# ProPrj_rp-nano-4_2025-11-21.net
KiCad netlist of a schematic drawn in EasyEDA Pro
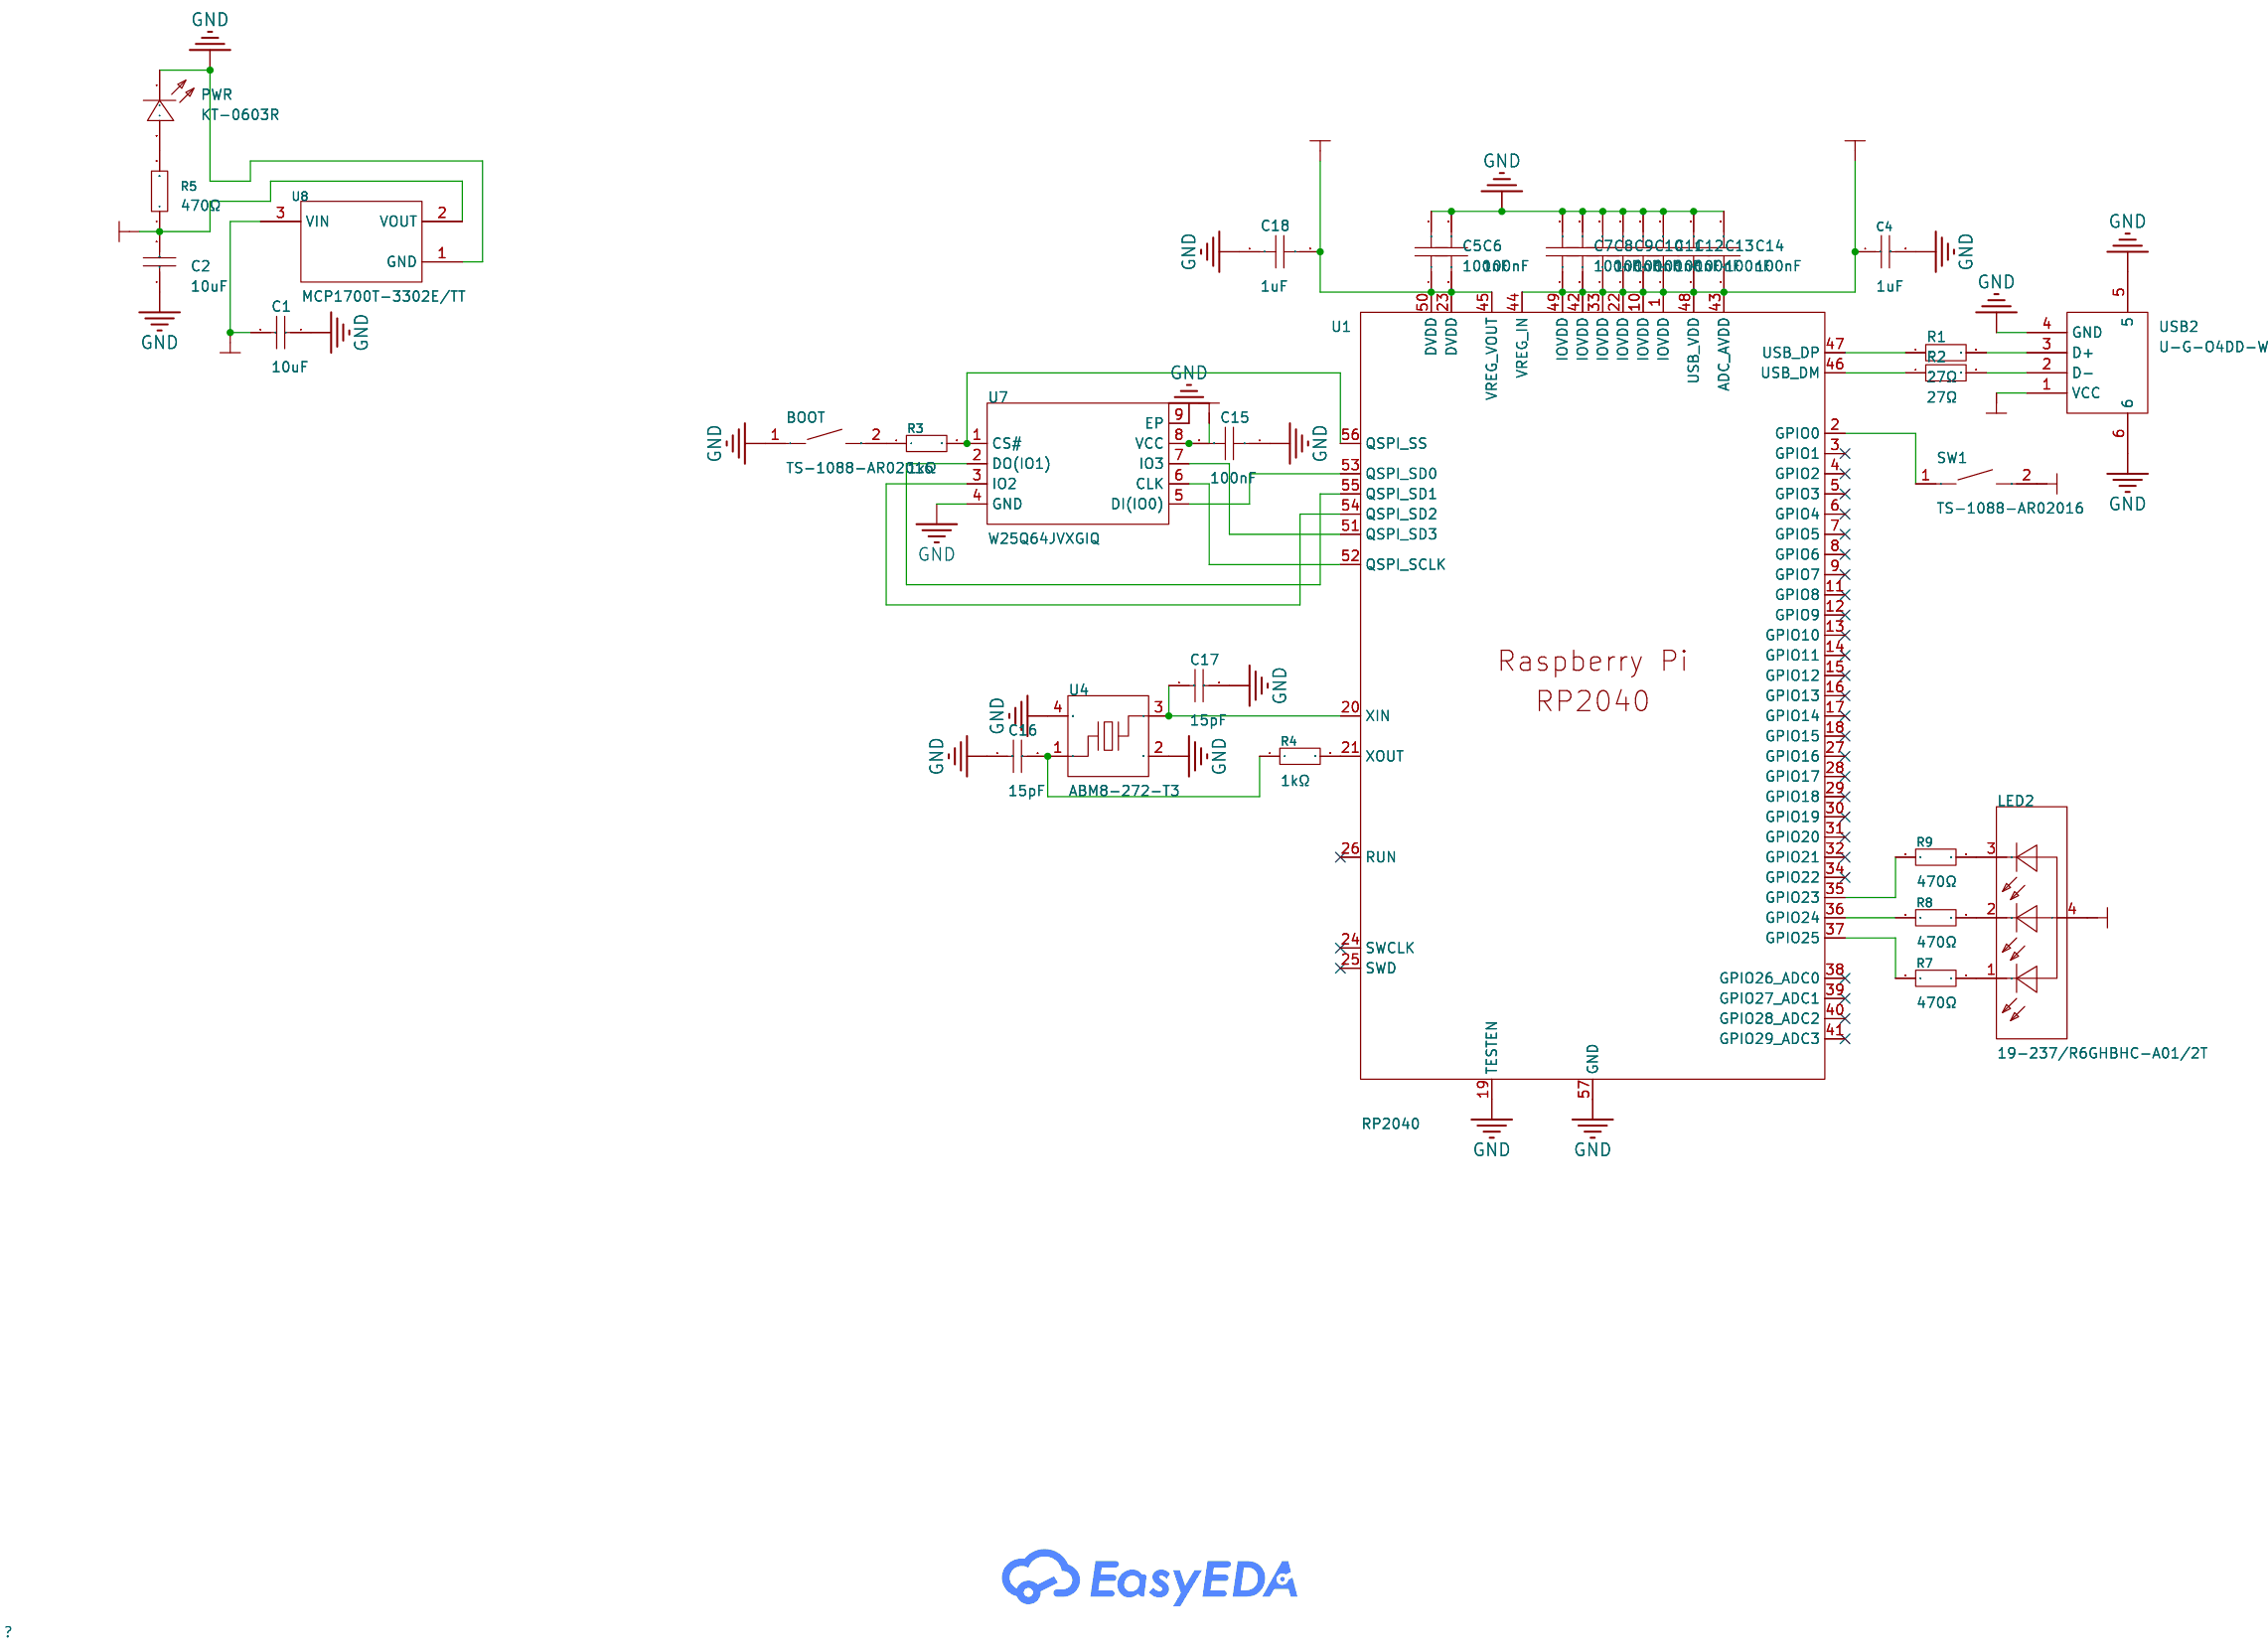
[diagram p0: schematic sheet]

(export (version "E")
  (design (tool "Eeschema 10.0.6"))
  (components
    (comp (ref "BOOT")
      (value "TS-1088-AR02016")
      (footprint "easyedapro:SW-SMD_L3.9-W3.0-P4.45")
      (fields (field (name "Manufacturer") "XUNPU(讯普)"))
      (libsource (lib "easyedapro") (part "TS-1088-AR02016"))
    )
    (comp (ref "C1")
      (value "10uF")
      (footprint "easyedapro:C0402")
      (fields
        (field (name "Manufacturer Part") "CL05A106MQ5NUNC")
        (field (name "Manufacturer") "SAMSUNG(三星)")
      )
      (libsource (lib "easyedapro") (part "CL05A106MQ5NUNC"))
    )
    (comp (ref "C2")
      (value "10uF")
      (footprint "easyedapro:C0402")
      (fields
        (field (name "Manufacturer Part") "CL05A106MQ5NUNC")
        (field (name "Manufacturer") "SAMSUNG(三星)")
      )
      (libsource (lib "easyedapro") (part "CL05A106MQ5NUNC"))
    )
    (comp (ref "C4")
      (value "1uF")
      (footprint "easyedapro:C0402")
      (fields
        (field (name "Manufacturer Part") "CL05A105KO5NNNC")
        (field (name "Manufacturer") "SAMSUNG(三星)")
      )
      (libsource (lib "easyedapro") (part "CL05A105KO5NNNC"))
    )
    (comp (ref "C5")
      (value "100nF")
      (footprint "easyedapro:C0402")
      (fields
        (field (name "Manufacturer Part") "CL05B104KO5NNNC")
        (field (name "Manufacturer") "SAMSUNG(三星)")
      )
      (libsource (lib "easyedapro") (part "CL05B104KO5NNNC"))
    )
    (comp (ref "C6")
      (value "100nF")
      (footprint "easyedapro:C0402")
      (fields
        (field (name "Manufacturer Part") "CL05B104KO5NNNC")
        (field (name "Manufacturer") "SAMSUNG(三星)")
      )
      (libsource (lib "easyedapro") (part "CL05B104KO5NNNC"))
    )
    (comp (ref "C7")
      (value "100nF")
      (footprint "easyedapro:C0402")
      (fields
        (field (name "Manufacturer Part") "CL05B104KO5NNNC")
        (field (name "Manufacturer") "SAMSUNG(三星)")
      )
      (libsource (lib "easyedapro") (part "CL05B104KO5NNNC"))
    )
    (comp (ref "C8")
      (value "100nF")
      (footprint "easyedapro:C0402")
      (fields
        (field (name "Manufacturer Part") "CL05B104KO5NNNC")
        (field (name "Manufacturer") "SAMSUNG(三星)")
      )
      (libsource (lib "easyedapro") (part "CL05B104KO5NNNC"))
    )
    (comp (ref "C9")
      (value "100nF")
      (footprint "easyedapro:C0402")
      (fields
        (field (name "Manufacturer Part") "CL05B104KO5NNNC")
        (field (name "Manufacturer") "SAMSUNG(三星)")
      )
      (libsource (lib "easyedapro") (part "CL05B104KO5NNNC"))
    )
    (comp (ref "C10")
      (value "100nF")
      (footprint "easyedapro:C0402")
      (fields
        (field (name "Manufacturer Part") "CL05B104KO5NNNC")
        (field (name "Manufacturer") "SAMSUNG(三星)")
      )
      (libsource (lib "easyedapro") (part "CL05B104KO5NNNC"))
    )
    (comp (ref "C11")
      (value "100nF")
      (footprint "easyedapro:C0402")
      (fields
        (field (name "Manufacturer Part") "CL05B104KO5NNNC")
        (field (name "Manufacturer") "SAMSUNG(三星)")
      )
      (libsource (lib "easyedapro") (part "CL05B104KO5NNNC"))
    )
    (comp (ref "C12")
      (value "100nF")
      (footprint "easyedapro:C0402")
      (fields
        (field (name "Manufacturer Part") "CL05B104KO5NNNC")
        (field (name "Manufacturer") "SAMSUNG(三星)")
      )
      (libsource (lib "easyedapro") (part "CL05B104KO5NNNC"))
    )
    (comp (ref "C13")
      (value "100nF")
      (footprint "easyedapro:C0402")
      (fields
        (field (name "Manufacturer Part") "CL05B104KO5NNNC")
        (field (name "Manufacturer") "SAMSUNG(三星)")
      )
      (libsource (lib "easyedapro") (part "CL05B104KO5NNNC"))
    )
    (comp (ref "C14")
      (value "100nF")
      (footprint "easyedapro:C0402")
      (fields
        (field (name "Manufacturer Part") "CL05B104KO5NNNC")
        (field (name "Manufacturer") "SAMSUNG(三星)")
      )
      (libsource (lib "easyedapro") (part "CL05B104KO5NNNC"))
    )
    (comp (ref "C15")
      (value "100nF")
      (footprint "easyedapro:C0402")
      (fields
        (field (name "Manufacturer Part") "CL05B104KO5NNNC")
        (field (name "Manufacturer") "SAMSUNG(三星)")
      )
      (libsource (lib "easyedapro") (part "CL05B104KO5NNNC"))
    )
    (comp (ref "C16")
      (value "15pF")
      (footprint "easyedapro:C0402")
      (fields (field (name "Manufacturer Part") "0402CG150J500NT") (field (name "Manufacturer") "FH(风华)"))
      (libsource (lib "easyedapro") (part "0402CG150J500NT"))
    )
    (comp (ref "C17")
      (value "15pF")
      (footprint "easyedapro:C0402")
      (fields (field (name "Manufacturer Part") "0402CG150J500NT") (field (name "Manufacturer") "FH(风华)"))
      (libsource (lib "easyedapro") (part "0402CG150J500NT"))
    )
    (comp (ref "C18")
      (value "1uF")
      (footprint "easyedapro:C0402")
      (fields
        (field (name "Manufacturer Part") "CL05A105KA5NQNC")
        (field (name "Manufacturer") "SAMSUNG(三星)")
      )
      (libsource (lib "easyedapro") (part "CL05A105KA5NQNC"))
    )
    (comp (ref "LED2")
      (value "19-237/R6GHBHC-A01/2T")
      (footprint "easyedapro:LED-ARRAY-SMD_4P-L1.6-W1.6-BL_1")
      (description "Diode Configuration:Common Anode Viewing Angle:120° Lens Color:-")
      (fields (field (name "Manufacturer") "EVERLIGHT(亿光)"))
      (libsource (lib "easyedapro") (part "19-237/R6GHBHC-A01/2T"))
    )
    (comp (ref "PWR")
      (value "KT-0603R")
      (footprint "easyedapro:LED0603-RD")
      (fields (field (name "Manufacturer") "KENTO"))
      (libsource (lib "easyedapro") (part "KT-0603R"))
    )
    (comp (ref "R1")
      (value "27Ω")
      (footprint "easyedapro:R0402")
      (fields
        (field (name "Manufacturer Part") "0402WGF270JTCE")
        (field (name "Manufacturer") "UNI-ROYAL(厚声)")
      )
      (libsource (lib "easyedapro") (part "0402WGF270JTCE"))
    )
    (comp (ref "R2")
      (value "27Ω")
      (footprint "easyedapro:R0402")
      (fields
        (field (name "Manufacturer Part") "0402WGF270JTCE")
        (field (name "Manufacturer") "UNI-ROYAL(厚声)")
      )
      (libsource (lib "easyedapro") (part "0402WGF270JTCE"))
    )
    (comp (ref "R3")
      (value "1kΩ")
      (footprint "easyedapro:R0402")
      (fields
        (field (name "Manufacturer Part") "0402WGF1001TCE")
        (field (name "Manufacturer") "UNI-ROYAL(厚声)")
      )
      (libsource (lib "easyedapro") (part "0402WGF1001TCE"))
    )
    (comp (ref "R4")
      (value "1kΩ")
      (footprint "easyedapro:R0402")
      (fields
        (field (name "Manufacturer Part") "0402WGF1001TCE")
        (field (name "Manufacturer") "UNI-ROYAL(厚声)")
      )
      (libsource (lib "easyedapro") (part "0402WGF1001TCE"))
    )
    (comp (ref "R5")
      (value "470Ω")
      (footprint "easyedapro:R0402")
      (fields
        (field (name "Manufacturer Part") "0402WGF4700TCE")
        (field (name "Manufacturer") "UNI-ROYAL(厚声)")
      )
      (libsource (lib "easyedapro") (part "0402WGF4700TCE"))
    )
    (comp (ref "R7")
      (value "470Ω")
      (footprint "easyedapro:R0402")
      (fields
        (field (name "Manufacturer Part") "0402WGF4700TCE")
        (field (name "Manufacturer") "UNI-ROYAL(厚声)")
      )
      (libsource (lib "easyedapro") (part "0402WGF4700TCE"))
    )
    (comp (ref "R8")
      (value "470Ω")
      (footprint "easyedapro:R0402")
      (fields
        (field (name "Manufacturer Part") "0402WGF4700TCE")
        (field (name "Manufacturer") "UNI-ROYAL(厚声)")
      )
      (libsource (lib "easyedapro") (part "0402WGF4700TCE"))
    )
    (comp (ref "R9")
      (value "470Ω")
      (footprint "easyedapro:R0402")
      (fields
        (field (name "Manufacturer Part") "0402WGF4700TCE")
        (field (name "Manufacturer") "UNI-ROYAL(厚声)")
      )
      (libsource (lib "easyedapro") (part "0402WGF4700TCE"))
    )
    (comp (ref "SW1")
      (value "TS-1088-AR02016")
      (footprint "easyedapro:SW-SMD_L3.9-W3.0-P4.45")
      (fields (field (name "Manufacturer") "XUNPU(讯普)"))
      (libsource (lib "easyedapro") (part "TS-1088-AR02016"))
    )
    (comp (ref "U1")
      (value "RP2040")
      (footprint "easyedapro:LQFN-56_L7.0-W7.0-P0.4-EP")
      (description "CPU Core:- CPU Maximum Speed:133MHz Number of I/O:30 ADC (Bit):12bit Applications:-")
      (fields (field (name "Manufacturer") "Raspberry Pi(树莓派)"))
      (libsource (lib "easyedapro") (part "RP2040"))
    )
    (comp (ref "U4")
      (value "ABM8-272-T3")
      (footprint "easyedapro:CRYSTAL-SMD_4P-L3.2-W2.5-BL")
      (fields (field (name "Manufacturer") "ABRACON"))
      (libsource (lib "easyedapro") (part "ABM8-272-T3_C20625731"))
    )
    (comp (ref "U7")
      (value "W25Q64JVXGIQ")
      (footprint "easyedapro:XSON-8_L4.0-W4.0-P0.80-TL-EP")
      (fields (field (name "Manufacturer") "Winbond(华邦)"))
      (libsource (lib "easyedapro") (part "W25Q64JVXGIQ"))
    )
    (comp (ref "U8")
      (value "MCP1700T-3302E/TT")
      (footprint "easyedapro:SOT-23-3_L2.9-W1.6-P1.90-LS2.8-BR")
      (fields (field (name "Manufacturer") "MICROCHIP(美国微芯)"))
      (libsource (lib "easyedapro") (part "MCP1700T-3302E/TT"))
    )
    (comp (ref "USB2")
      (value "U-G-O4DD-W-1")
      (footprint "easyedapro:USB-A-TH_U-G-04WD-W-01")
      (fields (field (name "Manufacturer") "韩国韩荣"))
      (libsource (lib "easyedapro") (part "U-G-04DD-W-01"))
    )
  )
  (nets
    (net (code "1") (name "GND") (class "Default")
      (node (ref "BOOT") (pin "1") (pinfunction "1_1") (pintype "unspecified"))
      (node (ref "C1") (pin "1") (pinfunction "1_1") (pintype "input"))
      (node (ref "C10") (pin "2") (pinfunction "2_2") (pintype "unspecified"))
      (node (ref "C11") (pin "2") (pinfunction "2_2") (pintype "unspecified"))
      (node (ref "C12") (pin "2") (pinfunction "2_2") (pintype "unspecified"))
      (node (ref "C13") (pin "2") (pinfunction "2_2") (pintype "unspecified"))
      (node (ref "C14") (pin "2") (pinfunction "2_2") (pintype "unspecified"))
      (node (ref "C15") (pin "1") (pinfunction "1_1") (pintype "unspecified"))
      (node (ref "C16") (pin "1") (pinfunction "1_1") (pintype "input"))
      (node (ref "C17") (pin "2") (pinfunction "2_2") (pintype "input"))
      (node (ref "C18") (pin "1") (pinfunction "1_1") (pintype "unspecified"))
      (node (ref "C2") (pin "1") (pinfunction "1_1") (pintype "input"))
      (node (ref "C4") (pin "2") (pinfunction "2_2") (pintype "input"))
      (node (ref "C5") (pin "2") (pinfunction "2_2") (pintype "unspecified"))
      (node (ref "C6") (pin "2") (pinfunction "2_2") (pintype "unspecified"))
      (node (ref "C7") (pin "2") (pinfunction "2_2") (pintype "unspecified"))
      (node (ref "C8") (pin "2") (pinfunction "2_2") (pintype "unspecified"))
      (node (ref "C9") (pin "2") (pinfunction "2_2") (pintype "unspecified"))
      (node (ref "PWR") (pin "1") (pinfunction "K_1") (pintype "unspecified"))
      (node (ref "U1") (pin "19") (pinfunction "TESTEN_19") (pintype "unspecified"))
      (node (ref "U1") (pin "57") (pinfunction "GND_57") (pintype "bidirectional"))
      (node (ref "U4") (pin "2") (pinfunction "GND_2") (pintype "input"))
      (node (ref "U4") (pin "4") (pinfunction "GND_4") (pintype "input"))
      (node (ref "U7") (pin "4") (pinfunction "GND_4") (pintype "unspecified"))
      (node (ref "U7") (pin "9") (pinfunction "EP_9") (pintype "unspecified"))
      (node (ref "U8") (pin "1") (pinfunction "GND_1") (pintype "input"))
      (node (ref "USB2") (pin "4") (pinfunction "GND_4") (pintype "unspecified"))
      (node (ref "USB2") (pin "5") (pinfunction "5_5") (pintype "unspecified"))
      (node (ref "USB2") (pin "6") (pinfunction "6_6") (pintype "unspecified"))
    )
    (net (code "2") (name "Net-(BOOT-Pad2)") (class "Default")
      (node (ref "BOOT") (pin "2") (pinfunction "2_2") (pintype "unspecified"))
      (node (ref "R3") (pin "1") (pinfunction "1_1") (pintype "input"))
    )
    (net (code "3") (name "Net-(C16-Pad2)") (class "Default")
      (node (ref "C16") (pin "2") (pinfunction "2_2") (pintype "input"))
      (node (ref "R4") (pin "1") (pinfunction "1_1") (pintype "input"))
      (node (ref "U4") (pin "1") (pinfunction "1_1") (pintype "input"))
    )
    (net (code "4") (name "Net-(LED2-B-)") (class "Default")
      (node (ref "LED2") (pin "3") (pinfunction "B-_3") (pintype "unspecified"))
      (node (ref "R9") (pin "1") (pinfunction "1_1") (pintype "input"))
    )
    (net (code "5") (name "Net-(LED2-G-)") (class "Default")
      (node (ref "LED2") (pin "2") (pinfunction "G-_2") (pintype "unspecified"))
      (node (ref "R8") (pin "1") (pinfunction "1_1") (pintype "input"))
    )
    (net (code "6") (name "Net-(LED2-R-)") (class "Default")
      (node (ref "LED2") (pin "1") (pinfunction "R-_1") (pintype "unspecified"))
      (node (ref "R7") (pin "1") (pinfunction "1_1") (pintype "input"))
    )
    (net (code "7") (name "Net-(PWR-A)") (class "Default")
      (node (ref "PWR") (pin "2") (pinfunction "A_2") (pintype "unspecified"))
      (node (ref "R5") (pin "2") (pinfunction "2_2") (pintype "input"))
    )
    (net (code "8") (name "Net-(U1-GPIO0)") (class "Default")
      (node (ref "SW1") (pin "1") (pinfunction "1_1") (pintype "unspecified"))
      (node (ref "U1") (pin "2") (pinfunction "GPIO0_2") (pintype "bidirectional"))
    )
    (net (code "9") (name "Net-(U1-GPIO23)") (class "Default")
      (node (ref "R9") (pin "2") (pinfunction "2_2") (pintype "input"))
      (node (ref "U1") (pin "35") (pinfunction "GPIO23_35") (pintype "bidirectional"))
    )
    (net (code "10") (name "Net-(U1-GPIO24)") (class "Default")
      (node (ref "R8") (pin "2") (pinfunction "2_2") (pintype "input"))
      (node (ref "U1") (pin "36") (pinfunction "GPIO24_36") (pintype "bidirectional"))
    )
    (net (code "11") (name "Net-(U1-GPIO25)") (class "Default")
      (node (ref "R7") (pin "2") (pinfunction "2_2") (pintype "input"))
      (node (ref "U1") (pin "37") (pinfunction "GPIO25_37") (pintype "bidirectional"))
    )
    (net (code "12") (name "Net-(U1-QSPI_SCLK)") (class "Default")
      (node (ref "U1") (pin "52") (pinfunction "QSPI_SCLK_52") (pintype "output"))
      (node (ref "U7") (pin "6") (pinfunction "CLK_6") (pintype "unspecified"))
    )
    (net (code "13") (name "Net-(U1-QSPI_SD0)") (class "Default")
      (node (ref "U1") (pin "53") (pinfunction "QSPI_SD0_53") (pintype "bidirectional"))
      (node (ref "U7") (pin "5") (pinfunction "DI(IO0)_5") (pintype "unspecified"))
    )
    (net (code "14") (name "Net-(U1-QSPI_SD1)") (class "Default")
      (node (ref "U1") (pin "55") (pinfunction "QSPI_SD1_55") (pintype "bidirectional"))
      (node (ref "U7") (pin "2") (pinfunction "DO(IO1)_2") (pintype "unspecified"))
    )
    (net (code "15") (name "Net-(U1-QSPI_SD2)") (class "Default")
      (node (ref "U1") (pin "54") (pinfunction "QSPI_SD2_54") (pintype "bidirectional"))
      (node (ref "U7") (pin "3") (pinfunction "IO2_3") (pintype "unspecified"))
    )
    (net (code "16") (name "Net-(U1-QSPI_SD3)") (class "Default")
      (node (ref "U1") (pin "51") (pinfunction "QSPI_SD3_51") (pintype "bidirectional"))
      (node (ref "U7") (pin "7") (pinfunction "IO3_7") (pintype "unspecified"))
    )
    (net (code "17") (name "Net-(U1-QSPI_SS)") (class "Default")
      (node (ref "R3") (pin "2") (pinfunction "2_2") (pintype "input"))
      (node (ref "U1") (pin "56") (pinfunction "QSPI_SS_56") (pintype "bidirectional"))
      (node (ref "U7") (pin "1") (pinfunction "CS#_1") (pintype "unspecified"))
    )
    (net (code "18") (name "Net-(U1-USB_DM)") (class "Default")
      (node (ref "R2") (pin "1") (pinfunction "1_1") (pintype "input"))
      (node (ref "U1") (pin "46") (pinfunction "USB_DM_46") (pintype "bidirectional"))
    )
    (net (code "19") (name "Net-(U1-USB_DP)") (class "Default")
      (node (ref "R1") (pin "1") (pinfunction "1_1") (pintype "input"))
      (node (ref "U1") (pin "47") (pinfunction "USB_DP_47") (pintype "bidirectional"))
    )
    (net (code "20") (name "Net-(U1-XIN)") (class "Default")
      (node (ref "C17") (pin "1") (pinfunction "1_1") (pintype "input"))
      (node (ref "U1") (pin "20") (pinfunction "XIN_20") (pintype "input"))
      (node (ref "U4") (pin "3") (pinfunction "3_3") (pintype "input"))
    )
    (net (code "21") (name "Net-(U1-XOUT)") (class "Default")
      (node (ref "R4") (pin "2") (pinfunction "2_2") (pintype "input"))
      (node (ref "U1") (pin "21") (pinfunction "XOUT_21") (pintype "unspecified"))
    )
    (net (code "22") (name "Net-(USB2-D+)") (class "Default")
      (node (ref "R1") (pin "2") (pinfunction "2_2") (pintype "input"))
      (node (ref "USB2") (pin "3") (pinfunction "D+_3") (pintype "unspecified"))
    )
    (net (code "23") (name "Net-(USB2-D-)") (class "Default")
      (node (ref "R2") (pin "2") (pinfunction "2_2") (pintype "input"))
      (node (ref "USB2") (pin "2") (pinfunction "D-_2") (pintype "unspecified"))
    )
    (net (code "24") (name "VCC_1V1") (class "Default")
      (node (ref "C18") (pin "2") (pinfunction "2_2") (pintype "unspecified"))
      (node (ref "C5") (pin "1") (pinfunction "1_1") (pintype "unspecified"))
      (node (ref "C6") (pin "1") (pinfunction "1_1") (pintype "unspecified"))
      (node (ref "U1") (pin "23") (pinfunction "DVDD_23") (pintype "bidirectional"))
      (node (ref "U1") (pin "45") (pinfunction "VREG_VOUT_45") (pintype "bidirectional"))
      (node (ref "U1") (pin "50") (pinfunction "DVDD_50") (pintype "bidirectional"))
    )
    (net (code "25") (name "VCC_3V3") (class "Default")
      (node (ref "C10") (pin "1") (pinfunction "1_1") (pintype "unspecified"))
      (node (ref "C11") (pin "1") (pinfunction "1_1") (pintype "unspecified"))
      (node (ref "C12") (pin "1") (pinfunction "1_1") (pintype "unspecified"))
      (node (ref "C13") (pin "1") (pinfunction "1_1") (pintype "unspecified"))
      (node (ref "C14") (pin "1") (pinfunction "1_1") (pintype "unspecified"))
      (node (ref "C15") (pin "2") (pinfunction "2_2") (pintype "unspecified"))
      (node (ref "C2") (pin "2") (pinfunction "2_2") (pintype "input"))
      (node (ref "C4") (pin "1") (pinfunction "1_1") (pintype "input"))
      (node (ref "C7") (pin "1") (pinfunction "1_1") (pintype "unspecified"))
      (node (ref "C8") (pin "1") (pinfunction "1_1") (pintype "unspecified"))
      (node (ref "C9") (pin "1") (pinfunction "1_1") (pintype "unspecified"))
      (node (ref "LED2") (pin "4") (pinfunction "+_4") (pintype "unspecified"))
      (node (ref "R5") (pin "1") (pinfunction "1_1") (pintype "input"))
      (node (ref "SW1") (pin "2") (pinfunction "2_2") (pintype "unspecified"))
      (node (ref "U1") (pin "1") (pinfunction "IOVDD_1") (pintype "bidirectional"))
      (node (ref "U1") (pin "10") (pinfunction "IOVDD_10") (pintype "bidirectional"))
      (node (ref "U1") (pin "22") (pinfunction "IOVDD_22") (pintype "bidirectional"))
      (node (ref "U1") (pin "33") (pinfunction "IOVDD_33") (pintype "bidirectional"))
      (node (ref "U1") (pin "42") (pinfunction "IOVDD_42") (pintype "bidirectional"))
      (node (ref "U1") (pin "43") (pinfunction "ADC_AVDD_43") (pintype "bidirectional"))
      (node (ref "U1") (pin "44") (pinfunction "VREG_IN_44") (pintype "bidirectional"))
      (node (ref "U1") (pin "48") (pinfunction "USB_VDD_48") (pintype "bidirectional"))
      (node (ref "U1") (pin "49") (pinfunction "IOVDD_49") (pintype "bidirectional"))
      (node (ref "U7") (pin "8") (pinfunction "VCC_8") (pintype "unspecified"))
      (node (ref "U8") (pin "2") (pinfunction "VOUT_2") (pintype "input"))
    )
    (net (code "26") (name "VCC_5V") (class "Default")
      (node (ref "C1") (pin "2") (pinfunction "2_2") (pintype "input"))
      (node (ref "U8") (pin "3") (pinfunction "VIN_3") (pintype "input"))
      (node (ref "USB2") (pin "1") (pinfunction "VCC_1") (pintype "unspecified"))
    )
    (net (code "27") (name "unconnected-(U1-GPIO1-Pad3)") (class "Default")
      (node (ref "U1") (pin "3") (pinfunction "GPIO1_3") (pintype "bidirectional+no_connect"))
    )
    (net (code "28") (name "unconnected-(U1-GPIO2-Pad4)") (class "Default")
      (node (ref "U1") (pin "4") (pinfunction "GPIO2_4") (pintype "bidirectional+no_connect"))
    )
    (net (code "29") (name "unconnected-(U1-GPIO3-Pad5)") (class "Default")
      (node (ref "U1") (pin "5") (pinfunction "GPIO3_5") (pintype "bidirectional+no_connect"))
    )
    (net (code "30") (name "unconnected-(U1-GPIO4-Pad6)") (class "Default")
      (node (ref "U1") (pin "6") (pinfunction "GPIO4_6") (pintype "bidirectional+no_connect"))
    )
    (net (code "31") (name "unconnected-(U1-GPIO5-Pad7)") (class "Default")
      (node (ref "U1") (pin "7") (pinfunction "GPIO5_7") (pintype "bidirectional+no_connect"))
    )
    (net (code "32") (name "unconnected-(U1-GPIO6-Pad8)") (class "Default")
      (node (ref "U1") (pin "8") (pinfunction "GPIO6_8") (pintype "bidirectional+no_connect"))
    )
    (net (code "33") (name "unconnected-(U1-GPIO7-Pad9)") (class "Default")
      (node (ref "U1") (pin "9") (pinfunction "GPIO7_9") (pintype "bidirectional+no_connect"))
    )
    (net (code "34") (name "unconnected-(U1-GPIO8-Pad11)") (class "Default")
      (node (ref "U1") (pin "11") (pinfunction "GPIO8_11") (pintype "bidirectional+no_connect"))
    )
    (net (code "35") (name "unconnected-(U1-GPIO9-Pad12)") (class "Default")
      (node (ref "U1") (pin "12") (pinfunction "GPIO9_12") (pintype "bidirectional+no_connect"))
    )
    (net (code "36") (name "unconnected-(U1-GPIO10-Pad13)") (class "Default")
      (node (ref "U1") (pin "13") (pinfunction "GPIO10_13") (pintype "bidirectional+no_connect"))
    )
    (net (code "37") (name "unconnected-(U1-GPIO11-Pad14)") (class "Default")
      (node (ref "U1") (pin "14") (pinfunction "GPIO11_14") (pintype "bidirectional+no_connect"))
    )
    (net (code "38") (name "unconnected-(U1-GPIO12-Pad15)") (class "Default")
      (node (ref "U1") (pin "15") (pinfunction "GPIO12_15") (pintype "bidirectional+no_connect"))
    )
    (net (code "39") (name "unconnected-(U1-GPIO13-Pad16)") (class "Default")
      (node (ref "U1") (pin "16") (pinfunction "GPIO13_16") (pintype "bidirectional+no_connect"))
    )
    (net (code "40") (name "unconnected-(U1-GPIO14-Pad17)") (class "Default")
      (node (ref "U1") (pin "17") (pinfunction "GPIO14_17") (pintype "bidirectional+no_connect"))
    )
    (net (code "41") (name "unconnected-(U1-GPIO15-Pad18)") (class "Default")
      (node (ref "U1") (pin "18") (pinfunction "GPIO15_18") (pintype "bidirectional+no_connect"))
    )
    (net (code "42") (name "unconnected-(U1-GPIO16-Pad27)") (class "Default")
      (node (ref "U1") (pin "27") (pinfunction "GPIO16_27") (pintype "bidirectional+no_connect"))
    )
    (net (code "43") (name "unconnected-(U1-GPIO17-Pad28)") (class "Default")
      (node (ref "U1") (pin "28") (pinfunction "GPIO17_28") (pintype "bidirectional+no_connect"))
    )
    (net (code "44") (name "unconnected-(U1-GPIO18-Pad29)") (class "Default")
      (node (ref "U1") (pin "29") (pinfunction "GPIO18_29") (pintype "bidirectional+no_connect"))
    )
    (net (code "45") (name "unconnected-(U1-GPIO19-Pad30)") (class "Default")
      (node (ref "U1") (pin "30") (pinfunction "GPIO19_30") (pintype "bidirectional+no_connect"))
    )
    (net (code "46") (name "unconnected-(U1-GPIO20-Pad31)") (class "Default")
      (node (ref "U1") (pin "31") (pinfunction "GPIO20_31") (pintype "bidirectional+no_connect"))
    )
    (net (code "47") (name "unconnected-(U1-GPIO21-Pad32)") (class "Default")
      (node (ref "U1") (pin "32") (pinfunction "GPIO21_32") (pintype "bidirectional+no_connect"))
    )
    (net (code "48") (name "unconnected-(U1-GPIO22-Pad34)") (class "Default")
      (node (ref "U1") (pin "34") (pinfunction "GPIO22_34") (pintype "bidirectional+no_connect"))
    )
    (net (code "49") (name "unconnected-(U1-GPIO26_ADC0-Pad38)") (class "Default")
      (node (ref "U1") (pin "38") (pinfunction "GPIO26_ADC0_38") (pintype "bidirectional+no_connect"))
    )
    (net (code "50") (name "unconnected-(U1-GPIO27_ADC1-Pad39)") (class "Default")
      (node (ref "U1") (pin "39") (pinfunction "GPIO27_ADC1_39") (pintype "bidirectional+no_connect"))
    )
    (net (code "51") (name "unconnected-(U1-GPIO28_ADC2-Pad40)") (class "Default")
      (node (ref "U1") (pin "40") (pinfunction "GPIO28_ADC2_40") (pintype "bidirectional+no_connect"))
    )
    (net (code "52") (name "unconnected-(U1-GPIO29_ADC3-Pad41)") (class "Default")
      (node (ref "U1") (pin "41") (pinfunction "GPIO29_ADC3_41") (pintype "bidirectional+no_connect"))
    )
    (net (code "53") (name "unconnected-(U1-RUN-Pad26)") (class "Default")
      (node (ref "U1") (pin "26") (pinfunction "RUN_26") (pintype "input+no_connect"))
    )
    (net (code "54") (name "unconnected-(U1-SWCLK-Pad24)") (class "Default")
      (node (ref "U1") (pin "24") (pinfunction "SWCLK_24") (pintype "output+no_connect"))
    )
    (net (code "55") (name "unconnected-(U1-SWD-Pad25)") (class "Default")
      (node (ref "U1") (pin "25") (pinfunction "SWD_25") (pintype "bidirectional+no_connect"))
    )
  )
)
